# cap_probe.net
KiCad netlist of a schematic drawn in EAGLE
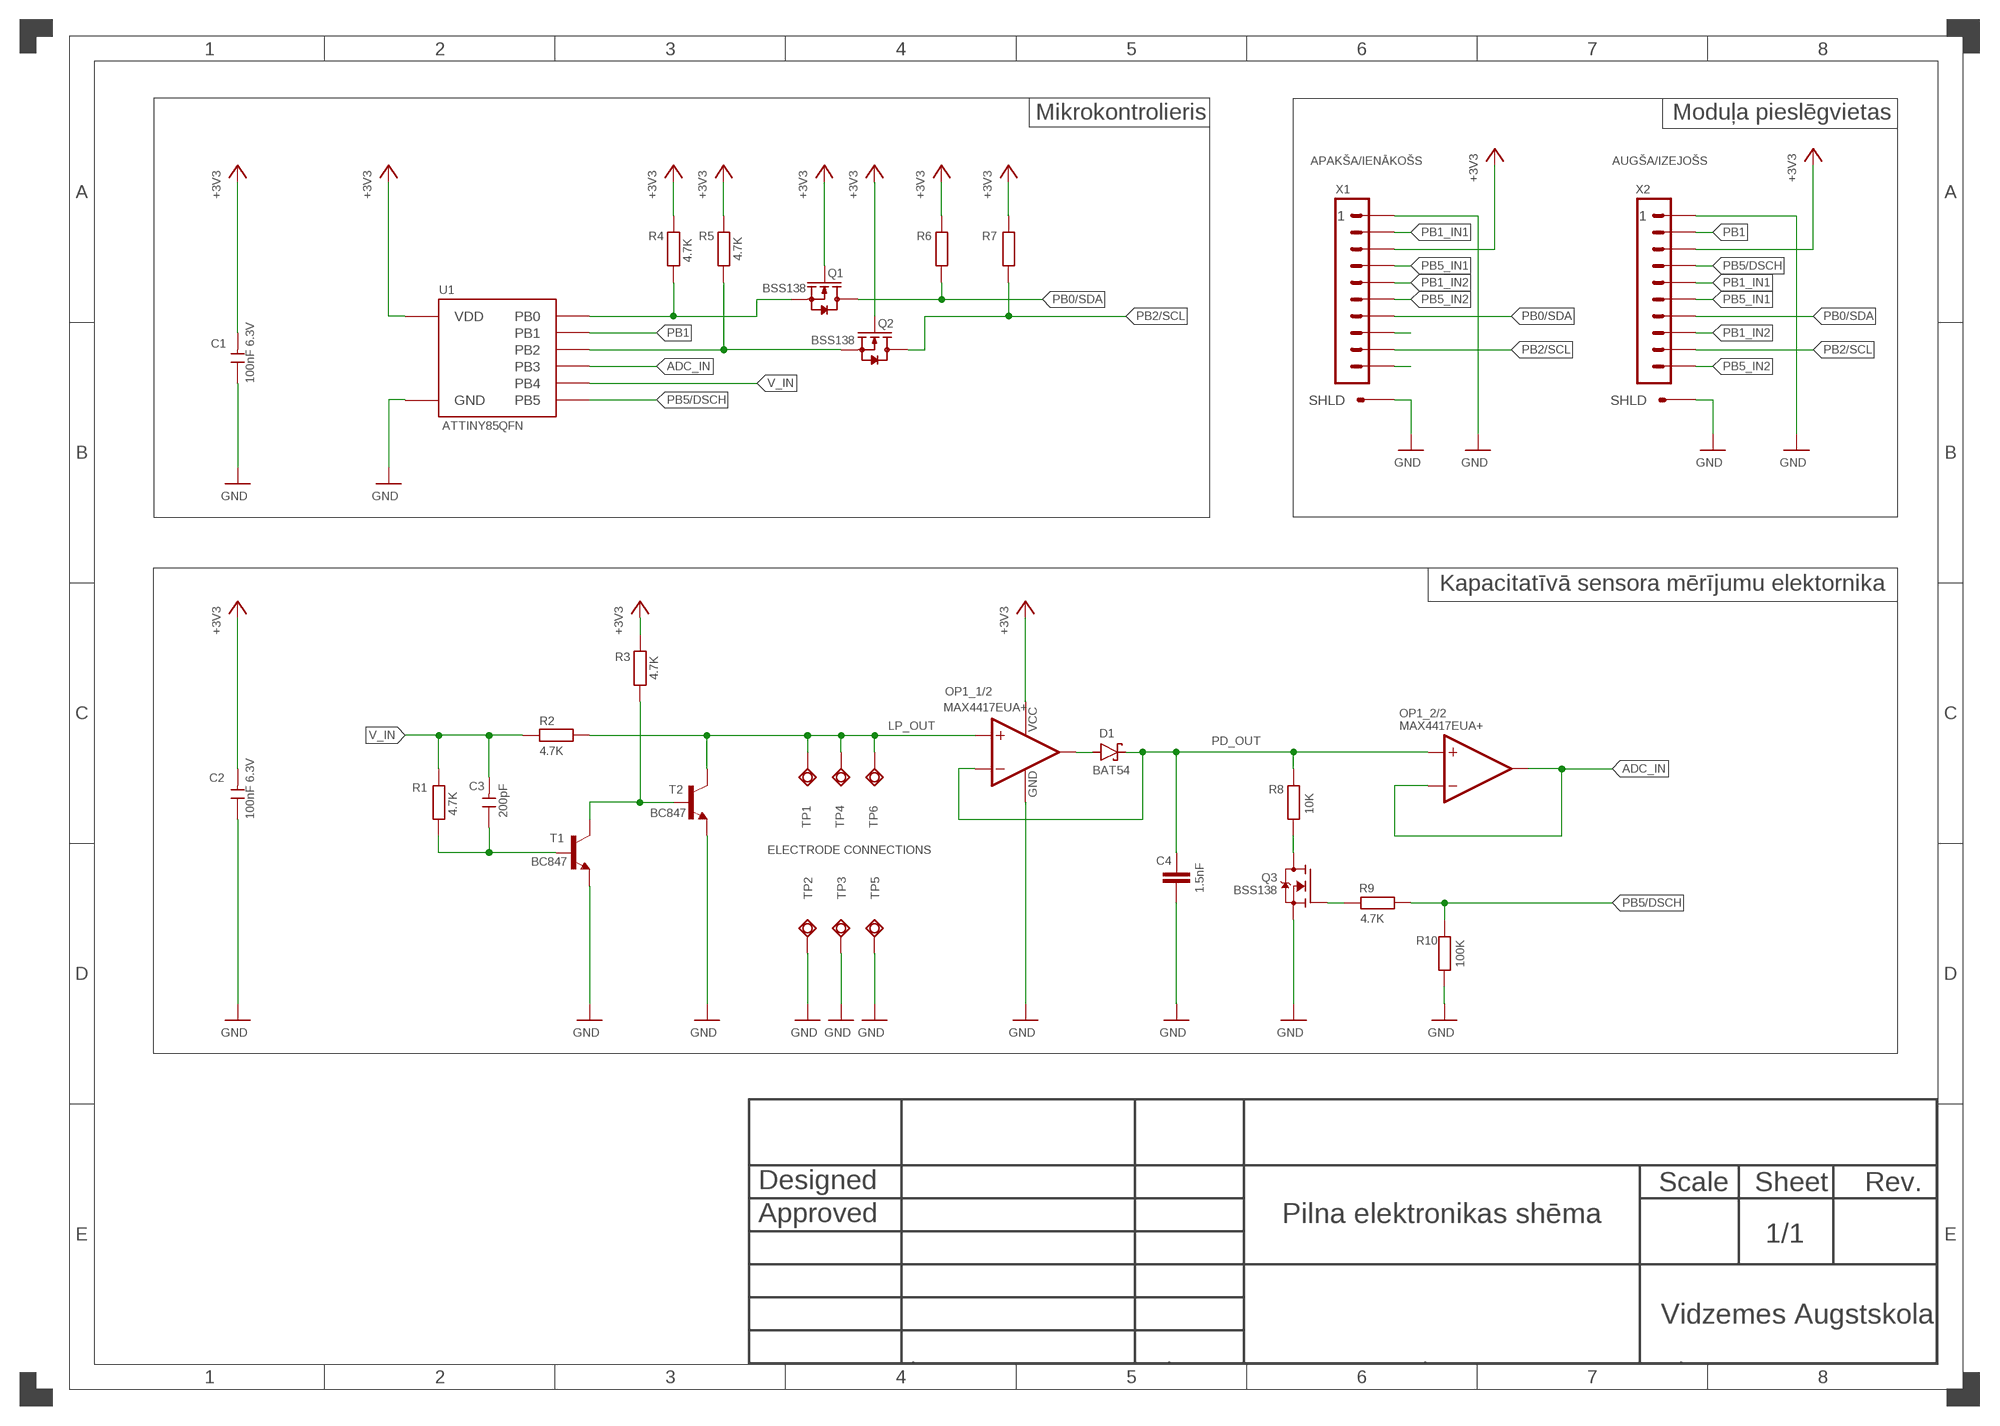
[diagram p0: schematic, sheet 1]

(export (version "E")
  (design (tool "Eeschema 10.0.6"))
  (components
    (comp (ref "C1")
      (value "100nF 6.3V")
      (footprint "eagle-import:C0402")
      (fields (field (name "MPN") "CC0402KRX5R5BB105"))
      (libsource (lib "eagle-import") (part "CERAMIC-1UF-6.3V-10%-X5R(0402)"))
    )
    (comp (ref "C2")
      (value "100nF 6.3V")
      (footprint "eagle-import:C0402")
      (fields (field (name "MPN") "CC0402KRX5R5BB105"))
      (libsource (lib "eagle-import") (part "CERAMIC-1UF-6.3V-10%-X5R(0402)"))
    )
    (comp (ref "C3")
      (value "200pF")
      (footprint "eagle-import:C0402")
      (fields (field (name "MPN") "CC0402KRX5R5BB105"))
      (libsource (lib "eagle-import") (part "CERAMIC-1UF-6.3V-10%-X5R(0402)"))
    )
    (comp (ref "C4")
      (value "1.5nF")
      (footprint "eagle-import:SMD_0603C")
      (libsource (lib "eagle-import") (part "CAP_CERAMIC_0603"))
    )
    (comp (ref "D1")
      (value "BAT54")
      (footprint "eagle-import:SOT23")
      (libsource (lib "eagle-import") (part "BAT54"))
    )
    (comp (ref "OP1")
      (value "MAX4417EUA+")
      (footprint "eagle-import:SOT23-8")
      (libsource (lib "eagle-import") (part "MAX_OP_AMPUMAX"))
    )
    (comp (ref "Q1")
      (value "BSS138")
      (footprint "eagle-import:SOT-23")
      (fields (field (name "MPN") "BSS138W-7-F"))
      (libsource (lib "eagle-import") (part "SMD-MOSFET-N-CH-50V-200MA-BSS138W-7-F(SOT-23)"))
    )
    (comp (ref "Q2")
      (value "BSS138")
      (footprint "eagle-import:SOT-23")
      (fields (field (name "MPN") "BSS138W-7-F"))
      (libsource (lib "eagle-import") (part "SMD-MOSFET-N-CH-50V-200MA-BSS138W-7-F(SOT-23)"))
    )
    (comp (ref "Q3")
      (value "BSS138")
      (footprint "eagle-import:SOT-23-3")
      (libsource (lib "eagle-import") (part "BSS138"))
    )
    (comp (ref "R1")
      (value "4.7K")
      (footprint "eagle-import:R0402")
      (libsource (lib "eagle-import") (part "RESISTOR_0402"))
    )
    (comp (ref "R2")
      (value "4.7K")
      (footprint "eagle-import:SMD_0603")
      (libsource (lib "eagle-import") (part "RESISTOR_0603"))
    )
    (comp (ref "R3")
      (value "4.7K")
      (footprint "eagle-import:R0402")
      (libsource (lib "eagle-import") (part "RESISTOR_0402"))
    )
    (comp (ref "R4")
      (value "4.7K")
      (footprint "eagle-import:R0402")
      (libsource (lib "eagle-import") (part "RESISTOR_0402"))
    )
    (comp (ref "R5")
      (value "4.7K")
      (footprint "eagle-import:R0402")
      (libsource (lib "eagle-import") (part "RESISTOR_0402"))
    )
    (comp (ref "R6")
      (value "RESISTOR_0402")
      (footprint "eagle-import:R0402")
      (libsource (lib "eagle-import") (part "RESISTOR_0402"))
    )
    (comp (ref "R7")
      (value "RESISTOR_0402")
      (footprint "eagle-import:R0402")
      (libsource (lib "eagle-import") (part "RESISTOR_0402"))
    )
    (comp (ref "R8")
      (value "10K")
      (footprint "eagle-import:R0402")
      (libsource (lib "eagle-import") (part "RESISTOR_0402"))
    )
    (comp (ref "R9")
      (value "4.7K")
      (footprint "eagle-import:R0402")
      (libsource (lib "eagle-import") (part "RESISTOR_0402"))
    )
    (comp (ref "R10")
      (value "100K")
      (footprint "eagle-import:R0402")
      (libsource (lib "eagle-import") (part "RESISTOR_0402"))
    )
    (comp (ref "T1")
      (value "BC847")
      (footprint "eagle-import:SOT23")
      (libsource (lib "eagle-import") (part "BC847"))
    )
    (comp (ref "T2")
      (value "BC847")
      (footprint "eagle-import:SOT23")
      (libsource (lib "eagle-import") (part "BC847"))
    )
    (comp (ref "TP1")
      (value "PAD1.5X3.0")
      (footprint "eagle-import:PAD1.5X3.0")
      (libsource (lib "eagle-import") (part "PAD1.5X3.0"))
    )
    (comp (ref "TP2")
      (value "PAD1.5X3.0")
      (footprint "eagle-import:PAD1.5X3.0")
      (libsource (lib "eagle-import") (part "PAD1.5X3.0"))
    )
    (comp (ref "TP3")
      (value "PAD1.5X3.0")
      (footprint "eagle-import:PAD1.5X3.0")
      (libsource (lib "eagle-import") (part "PAD1.5X3.0"))
    )
    (comp (ref "TP4")
      (value "PAD1.5X3.0")
      (footprint "eagle-import:PAD1.5X3.0")
      (libsource (lib "eagle-import") (part "PAD1.5X3.0"))
    )
    (comp (ref "TP5")
      (value "PAD1.5X3.0")
      (footprint "eagle-import:PAD1.5X3.0")
      (libsource (lib "eagle-import") (part "PAD1.5X3.0"))
    )
    (comp (ref "TP6")
      (value "PAD1.5X3.0")
      (footprint "eagle-import:PAD1.5X3.0")
      (libsource (lib "eagle-import") (part "PAD1.5X3.0"))
    )
    (comp (ref "U1")
      (value "ATTINY85QFN")
      (footprint "eagle-import:QFN20_4X4")
      (libsource (lib "eagle-import") (part "ATTINY85QFN"))
    )
    (comp (ref "X1")
      (value "FFC_10PH")
      (footprint "eagle-import:FFC_1.0X10")
      (libsource (lib "eagle-import") (part "FFC_10PH"))
    )
    (comp (ref "X2")
      (value "FFC_10PH")
      (footprint "eagle-import:FFC_1.0X10")
      (libsource (lib "eagle-import") (part "FFC_10PH"))
    )
  )
  (nets
    (net (code "1") (name "+3V3") (class "Default")
      (node (ref "C1") (pin "2") (pinfunction "2_2") (pintype "passive"))
      (node (ref "C2") (pin "2") (pinfunction "2_2") (pintype "passive"))
      (node (ref "OP1") (pin "P$8") (pinfunction "V+_P$8") (pintype "power_in"))
      (node (ref "Q1") (pin "1") (pinfunction "G_1") (pintype "passive"))
      (node (ref "Q2") (pin "1") (pinfunction "G_1") (pintype "passive"))
      (node (ref "R3") (pin "2") (pinfunction "2_2") (pintype "passive"))
      (node (ref "R4") (pin "2") (pinfunction "2_2") (pintype "passive"))
      (node (ref "R5") (pin "2") (pinfunction "2_2") (pintype "passive"))
      (node (ref "R6") (pin "2") (pinfunction "2_2") (pintype "passive"))
      (node (ref "R7") (pin "2") (pinfunction "2_2") (pintype "passive"))
      (node (ref "U1") (pin "P$15") (pinfunction "VDD_P$15") (pintype "bidirectional"))
      (node (ref "X1") (pin "P$3") (pinfunction "3_P$3") (pintype "passive"))
      (node (ref "X2") (pin "P$3") (pinfunction "3_P$3") (pintype "passive"))
    )
    (net (code "2") (name "/LP_OUT") (class "Default")
      (node (ref "OP1") (pin "P$3") (pinfunction "+IN_P$3") (pintype "input"))
      (node (ref "R2") (pin "2") (pinfunction "2_2") (pintype "passive"))
      (node (ref "T2") (pin "3") (pinfunction "C_3") (pintype "passive"))
      (node (ref "TP1") (pin "P$1") (pinfunction "P$1_P$1") (pintype "bidirectional"))
      (node (ref "TP4") (pin "P$1") (pinfunction "P$1_P$1") (pintype "bidirectional"))
      (node (ref "TP6") (pin "P$1") (pinfunction "P$1_P$1") (pintype "bidirectional"))
    )
    (net (code "3") (name "/PD_OUT") (class "Default")
      (node (ref "C4") (pin "1") (pinfunction "1_1") (pintype "passive"))
      (node (ref "D1") (pin "3") (pinfunction "C_3") (pintype "passive"))
      (node (ref "OP1") (pin "P$2") (pinfunction "-IN_P$2") (pintype "input"))
      (node (ref "OP1") (pin "P$5") (pinfunction "+IN_P$5") (pintype "input"))
      (node (ref "R8") (pin "2") (pinfunction "2_2") (pintype "passive"))
    )
    (net (code "4") (name "ADC_IN") (class "Default")
      (node (ref "OP1") (pin "P$6") (pinfunction "-IN_P$6") (pintype "input"))
      (node (ref "OP1") (pin "P$7") (pinfunction "OUT_P$7") (pintype "output"))
      (node (ref "U1") (pin "P$2") (pinfunction "PB3_P$2") (pintype "bidirectional"))
    )
    (net (code "5") (name "GND") (class "Default")
      (node (ref "C1") (pin "1") (pinfunction "1_1") (pintype "passive"))
      (node (ref "C2") (pin "1") (pinfunction "1_1") (pintype "passive"))
      (node (ref "C4") (pin "2") (pinfunction "2_2") (pintype "passive"))
      (node (ref "OP1") (pin "P$4") (pinfunction "V-_P$4") (pintype "power_in"))
      (node (ref "Q3") (pin "2") (pinfunction "S_2") (pintype "bidirectional"))
      (node (ref "R10") (pin "2") (pinfunction "2_2") (pintype "passive"))
      (node (ref "T1") (pin "2") (pinfunction "E_2") (pintype "passive"))
      (node (ref "T2") (pin "2") (pinfunction "E_2") (pintype "passive"))
      (node (ref "TP2") (pin "P$1") (pinfunction "P$1_P$1") (pintype "bidirectional"))
      (node (ref "TP3") (pin "P$1") (pinfunction "P$1_P$1") (pintype "bidirectional"))
      (node (ref "TP5") (pin "P$1") (pinfunction "P$1_P$1") (pintype "bidirectional"))
      (node (ref "U1") (pin "P$21") (pinfunction "GND_P$21") (pintype "bidirectional"))
      (node (ref "U1") (pin "P$8") (pinfunction "GND_P$8") (pintype "bidirectional"))
      (node (ref "X1") (pin "P$1") (pinfunction "1_P$1") (pintype "passive"))
      (node (ref "X1") (pin "P$11") (pinfunction "SHLD_P$11") (pintype "bidirectional"))
      (node (ref "X1") (pin "P$12") (pinfunction "SHLD_P$12") (pintype "bidirectional"))
      (node (ref "X2") (pin "P$1") (pinfunction "1_P$1") (pintype "passive"))
      (node (ref "X2") (pin "P$11") (pinfunction "SHLD_P$11") (pintype "bidirectional"))
      (node (ref "X2") (pin "P$12") (pinfunction "SHLD_P$12") (pintype "bidirectional"))
    )
    (net (code "6") (name "Net-(D1-A)") (class "Default")
      (node (ref "D1") (pin "1") (pinfunction "A_1") (pintype "passive"))
      (node (ref "OP1") (pin "P$1") (pinfunction "OUT_P$1") (pintype "output"))
    )
    (net (code "7") (name "Net-(Q1-S)") (class "Default")
      (node (ref "Q1") (pin "2") (pinfunction "S_2") (pintype "passive"))
      (node (ref "R4") (pin "1") (pinfunction "1_1") (pintype "passive"))
      (node (ref "U1") (pin "P$11") (pinfunction "PB0_P$11") (pintype "bidirectional"))
    )
    (net (code "8") (name "Net-(Q2-S)") (class "Default")
      (node (ref "Q2") (pin "2") (pinfunction "S_2") (pintype "passive"))
      (node (ref "R5") (pin "1") (pinfunction "1_1") (pintype "passive"))
      (node (ref "U1") (pin "P$14") (pinfunction "PB2_P$14") (pintype "bidirectional"))
    )
    (net (code "9") (name "Net-(Q3-D)") (class "Default")
      (node (ref "Q3") (pin "3") (pinfunction "D_3") (pintype "bidirectional"))
      (node (ref "R8") (pin "1") (pinfunction "1_1") (pintype "passive"))
    )
    (net (code "10") (name "Net-(Q3-G)") (class "Default")
      (node (ref "Q3") (pin "1") (pinfunction "G_1") (pintype "bidirectional"))
      (node (ref "R9") (pin "2") (pinfunction "2_2") (pintype "passive"))
    )
    (net (code "11") (name "Net-(T1-B)") (class "Default")
      (node (ref "C3") (pin "1") (pinfunction "1_1") (pintype "passive"))
      (node (ref "R1") (pin "1") (pinfunction "1_1") (pintype "passive"))
      (node (ref "T1") (pin "1") (pinfunction "B_1") (pintype "passive"))
    )
    (net (code "12") (name "Net-(T1-C)") (class "Default")
      (node (ref "R3") (pin "1") (pinfunction "1_1") (pintype "passive"))
      (node (ref "T1") (pin "3") (pinfunction "C_3") (pintype "passive"))
      (node (ref "T2") (pin "1") (pinfunction "B_1") (pintype "passive"))
    )
    (net (code "13") (name "PB0{slash}SDA") (class "Default")
      (node (ref "Q1") (pin "3") (pinfunction "D_3") (pintype "passive"))
      (node (ref "R6") (pin "1") (pinfunction "1_1") (pintype "passive"))
      (node (ref "X1") (pin "P$7") (pinfunction "7_P$7") (pintype "passive"))
      (node (ref "X2") (pin "P$7") (pinfunction "7_P$7") (pintype "passive"))
    )
    (net (code "14") (name "PB1") (class "Default")
      (node (ref "U1") (pin "P$12") (pinfunction "PB1_P$12") (pintype "bidirectional"))
      (node (ref "X2") (pin "P$2") (pinfunction "2_P$2") (pintype "passive"))
    )
    (net (code "15") (name "PB1_IN1") (class "Default")
      (node (ref "X1") (pin "P$2") (pinfunction "2_P$2") (pintype "passive"))
      (node (ref "X2") (pin "P$5") (pinfunction "5_P$5") (pintype "passive"))
    )
    (net (code "16") (name "PB1_IN2") (class "Default")
      (node (ref "X1") (pin "P$5") (pinfunction "5_P$5") (pintype "passive"))
      (node (ref "X2") (pin "P$8") (pinfunction "8_P$8") (pintype "passive"))
    )
    (net (code "17") (name "PB2{slash}SCL") (class "Default")
      (node (ref "Q2") (pin "3") (pinfunction "D_3") (pintype "passive"))
      (node (ref "R7") (pin "1") (pinfunction "1_1") (pintype "passive"))
      (node (ref "X1") (pin "P$9") (pinfunction "9_P$9") (pintype "passive"))
      (node (ref "X2") (pin "P$9") (pinfunction "9_P$9") (pintype "passive"))
    )
    (net (code "18") (name "PB5_IN1") (class "Default")
      (node (ref "X1") (pin "P$4") (pinfunction "4_P$4") (pintype "passive"))
      (node (ref "X2") (pin "P$6") (pinfunction "6_P$6") (pintype "passive"))
    )
    (net (code "19") (name "PB5_IN2") (class "Default")
      (node (ref "X1") (pin "P$6") (pinfunction "6_P$6") (pintype "passive"))
      (node (ref "X2") (pin "P$10") (pinfunction "10_P$10") (pintype "passive"))
    )
    (net (code "20") (name "PB5{slash}DSCH") (class "Default")
      (node (ref "R10") (pin "1") (pinfunction "1_1") (pintype "passive"))
      (node (ref "R9") (pin "1") (pinfunction "1_1") (pintype "passive"))
      (node (ref "U1") (pin "P$1") (pinfunction "PB5_P$1") (pintype "bidirectional"))
      (node (ref "X2") (pin "P$4") (pinfunction "4_P$4") (pintype "passive"))
    )
    (net (code "21") (name "V_IN") (class "Default")
      (node (ref "C3") (pin "2") (pinfunction "2_2") (pintype "passive"))
      (node (ref "R1") (pin "2") (pinfunction "2_2") (pintype "passive"))
      (node (ref "R2") (pin "1") (pinfunction "1_1") (pintype "passive"))
      (node (ref "U1") (pin "P$5") (pinfunction "PB4_P$5") (pintype "bidirectional"))
    )
    (net (code "22") (name "unconnected-(X1A-8-PadP$8)") (class "Default")
      (node (ref "X1") (pin "P$8") (pinfunction "8_P$8") (pintype "passive"))
    )
    (net (code "23") (name "unconnected-(X1A-10-PadP$10)") (class "Default")
      (node (ref "X1") (pin "P$10") (pinfunction "10_P$10") (pintype "passive"))
    )
  )
)
